# Thermocouple_datalogger_RevA.net
KiCad netlist of a schematic drawn in EAGLE
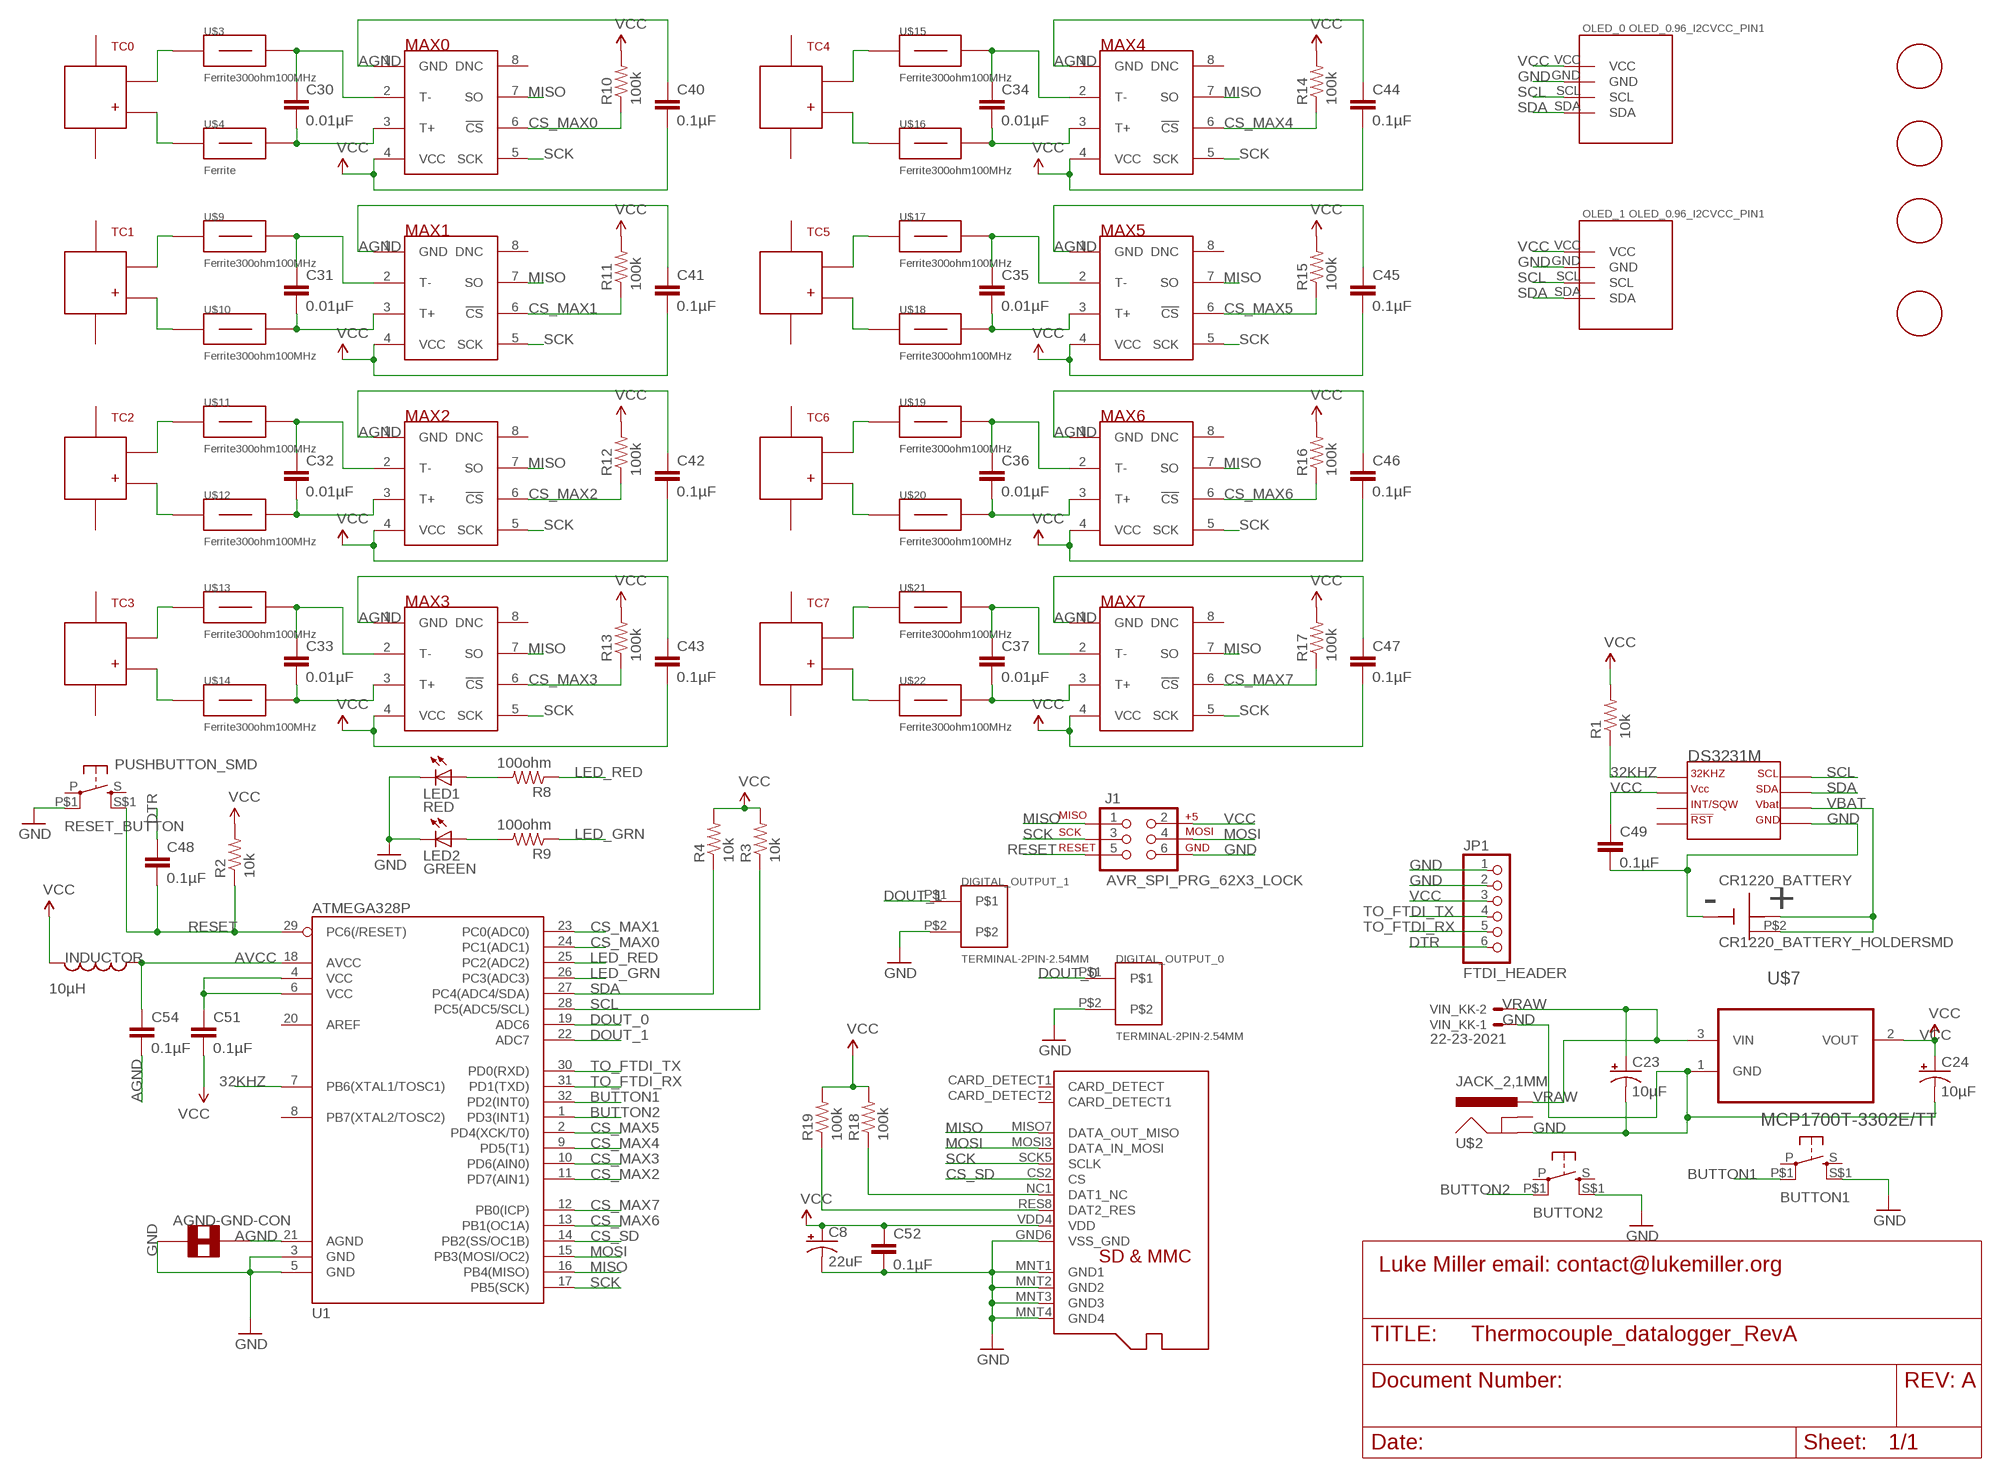
[diagram p0: schematic, sheet 1]

(export (version "E")
  (design (tool "Eeschema 10.0.6"))
  (components
    (comp (ref "AGND-GND-CON")
      (value "SOLDER_JUMPER_TRACESTANDARD")
      (footprint "eagle-import:SJ_2S-TRACE")
      (libsource (lib "eagle-import") (part "SOLDER_JUMPER_TRACESTANDARD"))
    )
    (comp (ref "BUTTON1")
      (value "PUSHBUTTON_DPST_SMDSTANDARD")
      (footprint "eagle-import:PUSHBUTTON_DPST_SMD")
      (libsource (lib "eagle-import") (part "PUSHBUTTON_DPST_SMDSTANDARD"))
    )
    (comp (ref "BUTTON2")
      (value "PUSHBUTTON_DPST_SMDSTANDARD")
      (footprint "eagle-import:PUSHBUTTON_DPST_SMD")
      (libsource (lib "eagle-import") (part "PUSHBUTTON_DPST_SMDSTANDARD"))
    )
    (comp (ref "C8")
      (value "22uF")
      (footprint "eagle-import:C0805_POL")
      (libsource (lib "eagle-import") (part "CPOL-US0805"))
    )
    (comp (ref "C23")
      (value "10µF")
      (footprint "eagle-import:PANASONIC_B")
      (libsource (lib "eagle-import") (part "CPOL-USB"))
    )
    (comp (ref "C24")
      (value "10µF")
      (footprint "eagle-import:PANASONIC_B")
      (libsource (lib "eagle-import") (part "CPOL-USB"))
    )
    (comp (ref "C30")
      (value "0.01µF")
      (footprint "eagle-import:0805")
      (libsource (lib "eagle-import") (part "CAP0805"))
    )
    (comp (ref "C31")
      (value "0.01µF")
      (footprint "eagle-import:0805")
      (libsource (lib "eagle-import") (part "CAP0805"))
    )
    (comp (ref "C32")
      (value "0.01µF")
      (footprint "eagle-import:0805")
      (libsource (lib "eagle-import") (part "CAP0805"))
    )
    (comp (ref "C33")
      (value "0.01µF")
      (footprint "eagle-import:0805")
      (libsource (lib "eagle-import") (part "CAP0805"))
    )
    (comp (ref "C34")
      (value "0.01µF")
      (footprint "eagle-import:0805")
      (libsource (lib "eagle-import") (part "CAP0805"))
    )
    (comp (ref "C35")
      (value "0.01µF")
      (footprint "eagle-import:0805")
      (libsource (lib "eagle-import") (part "CAP0805"))
    )
    (comp (ref "C36")
      (value "0.01µF")
      (footprint "eagle-import:0805")
      (libsource (lib "eagle-import") (part "CAP0805"))
    )
    (comp (ref "C37")
      (value "0.01µF")
      (footprint "eagle-import:0805")
      (libsource (lib "eagle-import") (part "CAP0805"))
    )
    (comp (ref "C40")
      (value "0.1µF")
      (footprint "eagle-import:0805")
      (libsource (lib "eagle-import") (part "CAP0805"))
    )
    (comp (ref "C41")
      (value "0.1µF")
      (footprint "eagle-import:0805")
      (libsource (lib "eagle-import") (part "CAP0805"))
    )
    (comp (ref "C42")
      (value "0.1µF")
      (footprint "eagle-import:0805")
      (libsource (lib "eagle-import") (part "CAP0805"))
    )
    (comp (ref "C43")
      (value "0.1µF")
      (footprint "eagle-import:0805")
      (libsource (lib "eagle-import") (part "CAP0805"))
    )
    (comp (ref "C44")
      (value "0.1µF")
      (footprint "eagle-import:0805")
      (libsource (lib "eagle-import") (part "CAP0805"))
    )
    (comp (ref "C45")
      (value "0.1µF")
      (footprint "eagle-import:0805")
      (libsource (lib "eagle-import") (part "CAP0805"))
    )
    (comp (ref "C46")
      (value "0.1µF")
      (footprint "eagle-import:0805")
      (libsource (lib "eagle-import") (part "CAP0805"))
    )
    (comp (ref "C47")
      (value "0.1µF")
      (footprint "eagle-import:0805")
      (libsource (lib "eagle-import") (part "CAP0805"))
    )
    (comp (ref "C48")
      (value "0.1µF")
      (footprint "eagle-import:0805")
      (libsource (lib "eagle-import") (part "CAP0805"))
    )
    (comp (ref "C49")
      (value "0.1µF")
      (footprint "eagle-import:0805")
      (libsource (lib "eagle-import") (part "CAP0805"))
    )
    (comp (ref "C51")
      (value "0.1µF")
      (footprint "eagle-import:0805")
      (libsource (lib "eagle-import") (part "CAP0805"))
    )
    (comp (ref "C52")
      (value "0.1µF")
      (footprint "eagle-import:0805")
      (libsource (lib "eagle-import") (part "CAP0805"))
    )
    (comp (ref "C54")
      (value "0.1µF")
      (footprint "eagle-import:0805")
      (libsource (lib "eagle-import") (part "CAP0805"))
    )
    (comp (ref "CR1220_BATTERY")
      (value "CR1220_BATTERY_HOLDERSMD")
      (footprint "eagle-import:CR1220_BATTERY_HOLDER_SMD")
      (libsource (lib "eagle-import") (part "CR1220_BATTERY_HOLDERSMD"))
    )
    (comp (ref "DIGITAL_OUTPUT_0")
      (value "TERMINAL-2PIN-2.54MM")
      (footprint "eagle-import:TERMINAL-2PIN-2.54MM")
      (libsource (lib "eagle-import") (part "TERMINAL-2PIN-2.54MM"))
    )
    (comp (ref "DIGITAL_OUTPUT_1")
      (value "TERMINAL-2PIN-2.54MM")
      (footprint "eagle-import:TERMINAL-2PIN-2.54MM")
      (libsource (lib "eagle-import") (part "TERMINAL-2PIN-2.54MM"))
    )
    (comp (ref "DS3231M")
      (value "DS3231MSOIC-8")
      (footprint "eagle-import:DS3231M_SOIC8")
      (libsource (lib "eagle-import") (part "DS3231MSOIC-8"))
    )
    (comp (ref "INDUCTOR")
      (value "10µH")
      (footprint "eagle-import:I_0805")
      (libsource (lib "eagle-import") (part "INDUCTOR0805_TY"))
    )
    (comp (ref "J1")
      (value "AVR_SPI_PRG_62X3_LOCK")
      (footprint "eagle-import:2X3_LOCK")
      (libsource (lib "eagle-import") (part "AVR_SPI_PRG_62X3_LOCK"))
    )
    (comp (ref "JP1")
      (value "FTDI_HEADER")
      (footprint "eagle-import:1X06-BIGLOCK")
      (libsource (lib "eagle-import") (part "PINHD-1X6LOCK"))
    )
    (comp (ref "LED1")
      (value "RED")
      (footprint "eagle-import:CHIPLED_0805")
      (libsource (lib "eagle-import") (part "LED0805"))
    )
    (comp (ref "LED2")
      (value "GREEN")
      (footprint "eagle-import:CHIPLED_0805")
      (libsource (lib "eagle-import") (part "LED0805"))
    )
    (comp (ref "MAX0")
      (value "MAX31855")
      (footprint "eagle-import:SO08")
      (libsource (lib "eagle-import") (part "MAX31855"))
    )
    (comp (ref "MAX1")
      (value "MAX31855")
      (footprint "eagle-import:SO08")
      (libsource (lib "eagle-import") (part "MAX31855"))
    )
    (comp (ref "MAX2")
      (value "MAX31855")
      (footprint "eagle-import:SO08")
      (libsource (lib "eagle-import") (part "MAX31855"))
    )
    (comp (ref "MAX3")
      (value "MAX31855")
      (footprint "eagle-import:SO08")
      (libsource (lib "eagle-import") (part "MAX31855"))
    )
    (comp (ref "MAX4")
      (value "MAX31855")
      (footprint "eagle-import:SO08")
      (libsource (lib "eagle-import") (part "MAX31855"))
    )
    (comp (ref "MAX5")
      (value "MAX31855")
      (footprint "eagle-import:SO08")
      (libsource (lib "eagle-import") (part "MAX31855"))
    )
    (comp (ref "MAX6")
      (value "MAX31855")
      (footprint "eagle-import:SO08")
      (libsource (lib "eagle-import") (part "MAX31855"))
    )
    (comp (ref "MAX7")
      (value "MAX31855")
      (footprint "eagle-import:SO08")
      (libsource (lib "eagle-import") (part "MAX31855"))
    )
    (comp (ref "OLED_0")
      (value "OLED_0.96_I2CVCC_PIN1")
      (footprint "eagle-import:OLED_0.96_I2C_VCC_PIN1")
      (libsource (lib "eagle-import") (part "OLED_0.96_I2CVCC_PIN1"))
    )
    (comp (ref "OLED_1")
      (value "OLED_0.96_I2CVCC_PIN1")
      (footprint "eagle-import:OLED_0.96_I2C_VCC_PIN1")
      (libsource (lib "eagle-import") (part "OLED_0.96_I2CVCC_PIN1"))
    )
    (comp (ref "R1")
      (value "10k")
      (footprint "eagle-import:R0805")
      (libsource (lib "eagle-import") (part "RESISTOR_SMDR0805"))
    )
    (comp (ref "R2")
      (value "10k")
      (footprint "eagle-import:R0805")
      (libsource (lib "eagle-import") (part "RESISTOR_SMDR0805"))
    )
    (comp (ref "R3")
      (value "10k")
      (footprint "eagle-import:R0805")
      (libsource (lib "eagle-import") (part "RESISTOR_SMDR0805"))
    )
    (comp (ref "R4")
      (value "10k")
      (footprint "eagle-import:R0805")
      (libsource (lib "eagle-import") (part "RESISTOR_SMDR0805"))
    )
    (comp (ref "R8")
      (value "100ohm")
      (footprint "eagle-import:R0805")
      (libsource (lib "eagle-import") (part "RESISTOR_SMDR0805"))
    )
    (comp (ref "R9")
      (value "100ohm")
      (footprint "eagle-import:R0805")
      (libsource (lib "eagle-import") (part "RESISTOR_SMDR0805"))
    )
    (comp (ref "R10")
      (value "100k")
      (footprint "eagle-import:R0805")
      (libsource (lib "eagle-import") (part "RESISTOR_SMDR0805"))
    )
    (comp (ref "R11")
      (value "100k")
      (footprint "eagle-import:R0805")
      (libsource (lib "eagle-import") (part "RESISTOR_SMDR0805"))
    )
    (comp (ref "R12")
      (value "100k")
      (footprint "eagle-import:R0805")
      (libsource (lib "eagle-import") (part "RESISTOR_SMDR0805"))
    )
    (comp (ref "R13")
      (value "100k")
      (footprint "eagle-import:R0805")
      (libsource (lib "eagle-import") (part "RESISTOR_SMDR0805"))
    )
    (comp (ref "R14")
      (value "100k")
      (footprint "eagle-import:R0805")
      (libsource (lib "eagle-import") (part "RESISTOR_SMDR0805"))
    )
    (comp (ref "R15")
      (value "100k")
      (footprint "eagle-import:R0805")
      (libsource (lib "eagle-import") (part "RESISTOR_SMDR0805"))
    )
    (comp (ref "R16")
      (value "100k")
      (footprint "eagle-import:R0805")
      (libsource (lib "eagle-import") (part "RESISTOR_SMDR0805"))
    )
    (comp (ref "R17")
      (value "100k")
      (footprint "eagle-import:R0805")
      (libsource (lib "eagle-import") (part "RESISTOR_SMDR0805"))
    )
    (comp (ref "R18")
      (value "100k")
      (footprint "eagle-import:R0805")
      (libsource (lib "eagle-import") (part "RESISTOR_SMDR0805"))
    )
    (comp (ref "R19")
      (value "100k")
      (footprint "eagle-import:R0805")
      (libsource (lib "eagle-import") (part "RESISTOR_SMDR0805"))
    )
    (comp (ref "RESET_BUTTON")
      (value "PUSHBUTTON_SMD")
      (footprint "eagle-import:PUSHBUTTON_DPST_SMD")
      (libsource (lib "eagle-import") (part "PUSHBUTTON_DPST_SMDSTANDARD"))
    )
    (comp (ref "TC0")
      (value "PCC-SMP-THERMOCOUPLEVERTICAL")
      (footprint "eagle-import:PCC-SMP-V")
      (libsource (lib "eagle-import") (part "PCC-SMP-THERMOCOUPLEVERTICAL"))
    )
    (comp (ref "TC1")
      (value "PCC-SMP-THERMOCOUPLEVERTICAL")
      (footprint "eagle-import:PCC-SMP-V")
      (libsource (lib "eagle-import") (part "PCC-SMP-THERMOCOUPLEVERTICAL"))
    )
    (comp (ref "TC2")
      (value "PCC-SMP-THERMOCOUPLEVERTICAL")
      (footprint "eagle-import:PCC-SMP-V")
      (libsource (lib "eagle-import") (part "PCC-SMP-THERMOCOUPLEVERTICAL"))
    )
    (comp (ref "TC3")
      (value "PCC-SMP-THERMOCOUPLEVERTICAL")
      (footprint "eagle-import:PCC-SMP-V")
      (libsource (lib "eagle-import") (part "PCC-SMP-THERMOCOUPLEVERTICAL"))
    )
    (comp (ref "TC4")
      (value "PCC-SMP-THERMOCOUPLEVERTICAL")
      (footprint "eagle-import:PCC-SMP-V")
      (libsource (lib "eagle-import") (part "PCC-SMP-THERMOCOUPLEVERTICAL"))
    )
    (comp (ref "TC5")
      (value "PCC-SMP-THERMOCOUPLEVERTICAL")
      (footprint "eagle-import:PCC-SMP-V")
      (libsource (lib "eagle-import") (part "PCC-SMP-THERMOCOUPLEVERTICAL"))
    )
    (comp (ref "TC6")
      (value "PCC-SMP-THERMOCOUPLEVERTICAL")
      (footprint "eagle-import:PCC-SMP-V")
      (libsource (lib "eagle-import") (part "PCC-SMP-THERMOCOUPLEVERTICAL"))
    )
    (comp (ref "TC7")
      (value "PCC-SMP-THERMOCOUPLEVERTICAL")
      (footprint "eagle-import:PCC-SMP-V")
      (libsource (lib "eagle-import") (part "PCC-SMP-THERMOCOUPLEVERTICAL"))
    )
    (comp (ref "U$2")
      (value "JACK_2,1MM")
      (footprint "eagle-import:POWER_JACK_DC_2,1MM")
      (libsource (lib "eagle-import") (part "POWER_JACK_2,1MM"))
    )
    (comp (ref "U$3")
      (value "Ferrite300ohm100MHz")
      (footprint "eagle-import:0805")
      (libsource (lib "eagle-import") (part "FERRITE_BEAD0805"))
    )
    (comp (ref "U$4")
      (value "Ferrite")
      (footprint "eagle-import:0805")
      (libsource (lib "eagle-import") (part "FERRITE_BEAD0805"))
    )
    (comp (ref "U$5")
      (value "MICROSD_MOLEX_REVERSECURRENT")
      (footprint "eagle-import:MICROSD_SOCKET_MOLEX_REVERSEMOUNT")
      (libsource (lib "eagle-import") (part "MICROSD_MOLEX_REVERSECURRENT"))
    )
    (comp (ref "U$6")
      (value "HOLE-LAYOUT4-40-SOCKET-HEAD")
      (footprint "eagle-import:4-40-SCREW-HOLE")
      (libsource (lib "eagle-import") (part "HOLE-LAYOUT4-40-SOCKET-HEAD"))
    )
    (comp (ref "U$7")
      (value "MCP1700T-3302E/TT")
      (footprint "eagle-import:SOT95P237X112-3N")
      (libsource (lib "eagle-import") (part "MCP1700T-3302E/TT"))
    )
    (comp (ref "U$9")
      (value "Ferrite300ohm100MHz")
      (footprint "eagle-import:0805")
      (libsource (lib "eagle-import") (part "FERRITE_BEAD0805"))
    )
    (comp (ref "U$10")
      (value "Ferrite300ohm100MHz")
      (footprint "eagle-import:0805")
      (libsource (lib "eagle-import") (part "FERRITE_BEAD0805"))
    )
    (comp (ref "U$11")
      (value "Ferrite300ohm100MHz")
      (footprint "eagle-import:0805")
      (libsource (lib "eagle-import") (part "FERRITE_BEAD0805"))
    )
    (comp (ref "U$12")
      (value "Ferrite300ohm100MHz")
      (footprint "eagle-import:0805")
      (libsource (lib "eagle-import") (part "FERRITE_BEAD0805"))
    )
    (comp (ref "U$13")
      (value "Ferrite300ohm100MHz")
      (footprint "eagle-import:0805")
      (libsource (lib "eagle-import") (part "FERRITE_BEAD0805"))
    )
    (comp (ref "U$14")
      (value "Ferrite300ohm100MHz")
      (footprint "eagle-import:0805")
      (libsource (lib "eagle-import") (part "FERRITE_BEAD0805"))
    )
    (comp (ref "U$15")
      (value "Ferrite300ohm100MHz")
      (footprint "eagle-import:0805")
      (libsource (lib "eagle-import") (part "FERRITE_BEAD0805"))
    )
    (comp (ref "U$16")
      (value "Ferrite300ohm100MHz")
      (footprint "eagle-import:0805")
      (libsource (lib "eagle-import") (part "FERRITE_BEAD0805"))
    )
    (comp (ref "U$17")
      (value "Ferrite300ohm100MHz")
      (footprint "eagle-import:0805")
      (libsource (lib "eagle-import") (part "FERRITE_BEAD0805"))
    )
    (comp (ref "U$18")
      (value "Ferrite300ohm100MHz")
      (footprint "eagle-import:0805")
      (libsource (lib "eagle-import") (part "FERRITE_BEAD0805"))
    )
    (comp (ref "U$19")
      (value "Ferrite300ohm100MHz")
      (footprint "eagle-import:0805")
      (libsource (lib "eagle-import") (part "FERRITE_BEAD0805"))
    )
    (comp (ref "U$20")
      (value "Ferrite300ohm100MHz")
      (footprint "eagle-import:0805")
      (libsource (lib "eagle-import") (part "FERRITE_BEAD0805"))
    )
    (comp (ref "U$21")
      (value "Ferrite300ohm100MHz")
      (footprint "eagle-import:0805")
      (libsource (lib "eagle-import") (part "FERRITE_BEAD0805"))
    )
    (comp (ref "U$22")
      (value "Ferrite300ohm100MHz")
      (footprint "eagle-import:0805")
      (libsource (lib "eagle-import") (part "FERRITE_BEAD0805"))
    )
    (comp (ref "U$23")
      (value "HOLE-LAYOUT4-40-SOCKET-HEAD")
      (footprint "eagle-import:4-40-SCREW-HOLE")
      (libsource (lib "eagle-import") (part "HOLE-LAYOUT4-40-SOCKET-HEAD"))
    )
    (comp (ref "U$24")
      (value "HOLE-LAYOUT4-40-SOCKET-HEAD")
      (footprint "eagle-import:4-40-SCREW-HOLE")
      (libsource (lib "eagle-import") (part "HOLE-LAYOUT4-40-SOCKET-HEAD"))
    )
    (comp (ref "U$25")
      (value "HOLE-LAYOUT4-40-SOCKET-HEAD")
      (footprint "eagle-import:4-40-SCREW-HOLE")
      (libsource (lib "eagle-import") (part "HOLE-LAYOUT4-40-SOCKET-HEAD"))
    )
    (comp (ref "U1")
      (value "ATMEGA328P")
      (footprint "eagle-import:TQFP32-08")
      (libsource (lib "eagle-import") (part "ATMEGA328_SMT"))
    )
    (comp (ref "VIN_KK")
      (value "22-23-2021")
      (footprint "eagle-import:22-23-2021")
      (fields (field (name "MF") "MOLEX"))
      (libsource (lib "eagle-import") (part "22-23-2021"))
    )
  )
  (nets
    (net (code "1") (name "/32KHZ") (class "Default")
      (node (ref "DS3231M") (pin "1") (pinfunction "P$1_32KHZ_1") (pintype "bidirectional"))
      (node (ref "R1") (pin "1") (pinfunction "1_1") (pintype "passive"))
      (node (ref "U1") (pin "7") (pinfunction "PB6(XTAL1/TOSC1)_7") (pintype "bidirectional"))
    )
    (net (code "2") (name "/AGND") (class "Default")
      (node (ref "AGND-GND-CON") (pin "2") (pinfunction "P$2_2") (pintype "bidirectional"))
      (node (ref "C40") (pin "1") (pinfunction "1_1") (pintype "passive"))
      (node (ref "C41") (pin "1") (pinfunction "1_1") (pintype "passive"))
      (node (ref "C42") (pin "1") (pinfunction "1_1") (pintype "passive"))
      (node (ref "C43") (pin "1") (pinfunction "1_1") (pintype "passive"))
      (node (ref "C44") (pin "1") (pinfunction "1_1") (pintype "passive"))
      (node (ref "C45") (pin "1") (pinfunction "1_1") (pintype "passive"))
      (node (ref "C46") (pin "1") (pinfunction "1_1") (pintype "passive"))
      (node (ref "C47") (pin "1") (pinfunction "1_1") (pintype "passive"))
      (node (ref "C54") (pin "2") (pinfunction "2_2") (pintype "passive"))
      (node (ref "MAX0") (pin "1") (pinfunction "GND_1") (pintype "power_in"))
      (node (ref "MAX1") (pin "1") (pinfunction "GND_1") (pintype "power_in"))
      (node (ref "MAX2") (pin "1") (pinfunction "GND_1") (pintype "power_in"))
      (node (ref "MAX3") (pin "1") (pinfunction "GND_1") (pintype "power_in"))
      (node (ref "MAX4") (pin "1") (pinfunction "GND_1") (pintype "power_in"))
      (node (ref "MAX5") (pin "1") (pinfunction "GND_1") (pintype "power_in"))
      (node (ref "MAX6") (pin "1") (pinfunction "GND_1") (pintype "power_in"))
      (node (ref "MAX7") (pin "1") (pinfunction "GND_1") (pintype "power_in"))
      (node (ref "U1") (pin "21") (pinfunction "AGND_21") (pintype "bidirectional"))
    )
    (net (code "3") (name "/AVCC") (class "Default")
      (node (ref "C54") (pin "1") (pinfunction "1_1") (pintype "passive"))
      (node (ref "INDUCTOR") (pin "P$1") (pinfunction "1_P$1") (pintype "passive"))
      (node (ref "U1") (pin "18") (pinfunction "AVCC_18") (pintype "bidirectional"))
    )
    (net (code "4") (name "/BUTTON1") (class "Default")
      (node (ref "BUTTON1") (pin "P$1") (pinfunction "P1_P$1") (pintype "passive"))
      (node (ref "U1") (pin "32") (pinfunction "PD2(INT0)_32") (pintype "bidirectional"))
    )
    (net (code "5") (name "/BUTTON2") (class "Default")
      (node (ref "BUTTON2") (pin "P$1") (pinfunction "P1_P$1") (pintype "passive"))
      (node (ref "U1") (pin "1") (pinfunction "PD3(INT1)_1") (pintype "bidirectional"))
    )
    (net (code "6") (name "/CS_MAX0") (class "Default")
      (node (ref "MAX0") (pin "6") (pinfunction "~{CS}_6") (pintype "bidirectional"))
      (node (ref "R10") (pin "1") (pinfunction "1_1") (pintype "passive"))
      (node (ref "U1") (pin "24") (pinfunction "PC1(ADC1)_24") (pintype "bidirectional"))
    )
    (net (code "7") (name "/CS_MAX1") (class "Default")
      (node (ref "MAX1") (pin "6") (pinfunction "~{CS}_6") (pintype "bidirectional"))
      (node (ref "R11") (pin "1") (pinfunction "1_1") (pintype "passive"))
      (node (ref "U1") (pin "23") (pinfunction "PC0(ADC0)_23") (pintype "bidirectional"))
    )
    (net (code "8") (name "/CS_MAX2") (class "Default")
      (node (ref "MAX2") (pin "6") (pinfunction "~{CS}_6") (pintype "bidirectional"))
      (node (ref "R12") (pin "1") (pinfunction "1_1") (pintype "passive"))
      (node (ref "U1") (pin "11") (pinfunction "PD7(AIN1)_11") (pintype "bidirectional"))
    )
    (net (code "9") (name "/CS_MAX3") (class "Default")
      (node (ref "MAX3") (pin "6") (pinfunction "~{CS}_6") (pintype "bidirectional"))
      (node (ref "R13") (pin "1") (pinfunction "1_1") (pintype "passive"))
      (node (ref "U1") (pin "10") (pinfunction "PD6(AIN0)_10") (pintype "bidirectional"))
    )
    (net (code "10") (name "/CS_MAX4") (class "Default")
      (node (ref "MAX4") (pin "6") (pinfunction "~{CS}_6") (pintype "bidirectional"))
      (node (ref "R14") (pin "1") (pinfunction "1_1") (pintype "passive"))
      (node (ref "U1") (pin "9") (pinfunction "PD5(T1)_9") (pintype "bidirectional"))
    )
    (net (code "11") (name "/CS_MAX5") (class "Default")
      (node (ref "MAX5") (pin "6") (pinfunction "~{CS}_6") (pintype "bidirectional"))
      (node (ref "R15") (pin "1") (pinfunction "1_1") (pintype "passive"))
      (node (ref "U1") (pin "2") (pinfunction "PD4(XCK/T0)_2") (pintype "bidirectional"))
    )
    (net (code "12") (name "/CS_MAX6") (class "Default")
      (node (ref "MAX6") (pin "6") (pinfunction "~{CS}_6") (pintype "bidirectional"))
      (node (ref "R16") (pin "1") (pinfunction "1_1") (pintype "passive"))
      (node (ref "U1") (pin "13") (pinfunction "PB1(OC1A)_13") (pintype "bidirectional"))
    )
    (net (code "13") (name "/CS_MAX7") (class "Default")
      (node (ref "MAX7") (pin "6") (pinfunction "~{CS}_6") (pintype "bidirectional"))
      (node (ref "R17") (pin "1") (pinfunction "1_1") (pintype "passive"))
      (node (ref "U1") (pin "12") (pinfunction "PB0(ICP)_12") (pintype "bidirectional"))
    )
    (net (code "14") (name "/CS_SD") (class "Default")
      (node (ref "U$5") (pin "CS2") (pinfunction "CS_CS2") (pintype "input"))
      (node (ref "U1") (pin "14") (pinfunction "PB2(SS/OC1B)_14") (pintype "bidirectional"))
    )
    (net (code "15") (name "/DOUT_0") (class "Default")
      (node (ref "DIGITAL_OUTPUT_0") (pin "P$1") (pinfunction "P$1_P$1") (pintype "bidirectional"))
      (node (ref "U1") (pin "19") (pinfunction "ADC6_19") (pintype "bidirectional"))
    )
    (net (code "16") (name "/DOUT_1") (class "Default")
      (node (ref "DIGITAL_OUTPUT_1") (pin "P$1") (pinfunction "P$1_P$1") (pintype "bidirectional"))
      (node (ref "U1") (pin "22") (pinfunction "ADC7_22") (pintype "bidirectional"))
    )
    (net (code "17") (name "/DTR") (class "Default")
      (node (ref "C48") (pin "1") (pinfunction "1_1") (pintype "passive"))
      (node (ref "JP1") (pin "6") (pinfunction "6_6") (pintype "passive"))
    )
    (net (code "18") (name "/LED_GRN") (class "Default")
      (node (ref "R9") (pin "1") (pinfunction "1_1") (pintype "passive"))
      (node (ref "U1") (pin "26") (pinfunction "PC3(ADC3)_26") (pintype "bidirectional"))
    )
    (net (code "19") (name "/LED_RED") (class "Default")
      (node (ref "R8") (pin "1") (pinfunction "1_1") (pintype "passive"))
      (node (ref "U1") (pin "25") (pinfunction "PC2(ADC2)_25") (pintype "bidirectional"))
    )
    (net (code "20") (name "/MISO") (class "Default")
      (node (ref "J1") (pin "1") (pinfunction "1_1") (pintype "passive"))
      (node (ref "MAX0") (pin "7") (pinfunction "SO_7") (pintype "bidirectional"))
      (node (ref "MAX1") (pin "7") (pinfunction "SO_7") (pintype "bidirectional"))
      (node (ref "MAX2") (pin "7") (pinfunction "SO_7") (pintype "bidirectional"))
      (node (ref "MAX3") (pin "7") (pinfunction "SO_7") (pintype "bidirectional"))
      (node (ref "MAX4") (pin "7") (pinfunction "SO_7") (pintype "bidirectional"))
      (node (ref "MAX5") (pin "7") (pinfunction "SO_7") (pintype "bidirectional"))
      (node (ref "MAX6") (pin "7") (pinfunction "SO_7") (pintype "bidirectional"))
      (node (ref "MAX7") (pin "7") (pinfunction "SO_7") (pintype "bidirectional"))
      (node (ref "U$5") (pin "MISO7") (pinfunction "DATA_OUT_MISO_MISO7") (pintype "output"))
      (node (ref "U1") (pin "16") (pinfunction "PB4(MISO)_16") (pintype "bidirectional"))
    )
    (net (code "21") (name "/MOSI") (class "Default")
      (node (ref "J1") (pin "4") (pinfunction "4_4") (pintype "passive"))
      (node (ref "U$5") (pin "MOSI3") (pinfunction "DATA_IN_MOSI_MOSI3") (pintype "input"))
      (node (ref "U1") (pin "15") (pinfunction "PB3(MOSI/OC2)_15") (pintype "bidirectional"))
    )
    (net (code "22") (name "/RESET") (class "Default")
      (node (ref "C48") (pin "2") (pinfunction "2_2") (pintype "passive"))
      (node (ref "J1") (pin "5") (pinfunction "5_5") (pintype "passive"))
      (node (ref "R2") (pin "1") (pinfunction "1_1") (pintype "passive"))
      (node (ref "RESET_BUTTON") (pin "S$1") (pinfunction "S1_S$1") (pintype "passive"))
      (node (ref "U1") (pin "29") (pinfunction "PC6(/RESET)_29") (pintype "bidirectional"))
    )
    (net (code "23") (name "/SCK") (class "Default")
      (node (ref "J1") (pin "3") (pinfunction "3_3") (pintype "passive"))
      (node (ref "MAX0") (pin "5") (pinfunction "SCK_5") (pintype "bidirectional"))
      (node (ref "MAX1") (pin "5") (pinfunction "SCK_5") (pintype "bidirectional"))
      (node (ref "MAX2") (pin "5") (pinfunction "SCK_5") (pintype "bidirectional"))
      (node (ref "MAX3") (pin "5") (pinfunction "SCK_5") (pintype "bidirectional"))
      (node (ref "MAX4") (pin "5") (pinfunction "SCK_5") (pintype "bidirectional"))
      (node (ref "MAX5") (pin "5") (pinfunction "SCK_5") (pintype "bidirectional"))
      (node (ref "MAX6") (pin "5") (pinfunction "SCK_5") (pintype "bidirectional"))
      (node (ref "MAX7") (pin "5") (pinfunction "SCK_5") (pintype "bidirectional"))
      (node (ref "U$5") (pin "SCK5") (pinfunction "SCLK_SCK5") (pintype "input"))
      (node (ref "U1") (pin "17") (pinfunction "PB5(SCK)_17") (pintype "bidirectional"))
    )
    (net (code "24") (name "/SCL") (class "Default")
      (node (ref "DS3231M") (pin "8") (pinfunction "P$8_SCL_8") (pintype "bidirectional"))
      (node (ref "OLED_0") (pin "SCL") (pinfunction "SCL_SCL") (pintype "bidirectional"))
      (node (ref "OLED_1") (pin "SCL") (pinfunction "SCL_SCL") (pintype "bidirectional"))
      (node (ref "R3") (pin "1") (pinfunction "1_1") (pintype "passive"))
      (node (ref "U1") (pin "28") (pinfunction "PC5(ADC5/SCL)_28") (pintype "bidirectional"))
    )
    (net (code "25") (name "/SDA") (class "Default")
      (node (ref "DS3231M") (pin "7") (pinfunction "P$7_SDA_7") (pintype "bidirectional"))
      (node (ref "OLED_0") (pin "SDA") (pinfunction "SDA_SDA") (pintype "bidirectional"))
      (node (ref "OLED_1") (pin "SDA") (pinfunction "SDA_SDA") (pintype "bidirectional"))
      (node (ref "R4") (pin "1") (pinfunction "1_1") (pintype "passive"))
      (node (ref "U1") (pin "27") (pinfunction "PC4(ADC4/SDA)_27") (pintype "bidirectional"))
    )
    (net (code "26") (name "/TO_FTDI_RX") (class "Default")
      (node (ref "JP1") (pin "5") (pinfunction "5_5") (pintype "passive"))
      (node (ref "U1") (pin "31") (pinfunction "PD1(TXD)_31") (pintype "bidirectional"))
    )
    (net (code "27") (name "/TO_FTDI_TX") (class "Default")
      (node (ref "JP1") (pin "4") (pinfunction "4_4") (pintype "passive"))
      (node (ref "U1") (pin "30") (pinfunction "PD0(RXD)_30") (pintype "bidirectional"))
    )
    (net (code "28") (name "/VBAT") (class "Default")
      (node (ref "CR1220_BATTERY") (pin "P$1") (pinfunction "VBAT_P$1") (pintype "power_in"))
      (node (ref "CR1220_BATTERY") (pin "P$2") (pinfunction "P$2_P$2") (pintype "power_in"))
      (node (ref "DS3231M") (pin "6") (pinfunction "P$6_VBAT_6") (pintype "bidirectional"))
    )
    (net (code "29") (name "/VRAW") (class "Default")
      (node (ref "C23") (pin "+") (pinfunction "+_+") (pintype "passive"))
      (node (ref "U$2") (pin "P$1") (pinfunction "PWR_P$1") (pintype "bidirectional"))
      (node (ref "U$7") (pin "3") (pinfunction "VIN_3") (pintype "input"))
      (node (ref "VIN_KK") (pin "2") (pinfunction "S_2") (pintype "passive"))
    )
    (net (code "30") (name "GND") (class "Default")
      (node (ref "AGND-GND-CON") (pin "1") (pinfunction "P$1_1") (pintype "bidirectional"))
      (node (ref "BUTTON1") (pin "S$1") (pinfunction "S1_S$1") (pintype "passive"))
      (node (ref "BUTTON2") (pin "S$1") (pinfunction "S1_S$1") (pintype "passive"))
      (node (ref "C23") (pin "-") (pinfunction "-_-") (pintype "passive"))
      (node (ref "C24") (pin "-") (pinfunction "-_-") (pintype "passive"))
      (node (ref "C49") (pin "2") (pinfunction "2_2") (pintype "passive"))
      (node (ref "C52") (pin "2") (pinfunction "2_2") (pintype "passive"))
      (node (ref "C8") (pin "P$2_C") (pinfunction "-_P$2_C") (pintype "passive"))
      (node (ref "CR1220_BATTERY") (pin "GND") (pinfunction "GND_GND") (pintype "power_in"))
      (node (ref "DIGITAL_OUTPUT_0") (pin "P$2") (pinfunction "P$2_P$2") (pintype "bidirectional"))
      (node (ref "DIGITAL_OUTPUT_1") (pin "P$2") (pinfunction "P$2_P$2") (pintype "bidirectional"))
      (node (ref "DS3231M") (pin "5") (pinfunction "P$5_GND_5") (pintype "power_in"))
      (node (ref "J1") (pin "6") (pinfunction "6_6") (pintype "passive"))
      (node (ref "JP1") (pin "1") (pinfunction "1_1") (pintype "passive"))
      (node (ref "JP1") (pin "2") (pinfunction "2_2") (pintype "passive"))
      (node (ref "LED1") (pin "C") (pinfunction "C_C") (pintype "passive"))
      (node (ref "LED2") (pin "C") (pinfunction "C_C") (pintype "passive"))
      (node (ref "OLED_0") (pin "GND") (pinfunction "GND_GND") (pintype "bidirectional"))
      (node (ref "OLED_1") (pin "GND") (pinfunction "GND_GND") (pintype "bidirectional"))
      (node (ref "RESET_BUTTON") (pin "P$1") (pinfunction "P1_P$1") (pintype "passive"))
      (node (ref "U$2") (pin "P$2") (pinfunction "GND_P$2") (pintype "bidirectional"))
      (node (ref "U$5") (pin "GND6") (pinfunction "VSS_GND_GND6") (pintype "power_in"))
      (node (ref "U$5") (pin "MNT1") (pinfunction "GND1_MNT1") (pintype "power_in"))
      (node (ref "U$5") (pin "MNT2") (pinfunction "GND2_MNT2") (pintype "power_in"))
      (node (ref "U$5") (pin "MNT3") (pinfunction "GND3_MNT3") (pintype "power_in"))
      (node (ref "U$5") (pin "MNT4") (pinfunction "GND4_MNT4") (pintype "power_in"))
      (node (ref "U$7") (pin "1") (pinfunction "GND_1") (pintype "passive"))
      (node (ref "U1") (pin "3") (pinfunction "GND_3") (pintype "bidirectional"))
      (node (ref "U1") (pin "5") (pinfunction "GND_5") (pintype "bidirectional"))
      (node (ref "VIN_KK") (pin "1") (pinfunction "S_1") (pintype "passive"))
    )
    (net (code "31") (name "Net-(C51-Pad1)") (class "Default")
      (node (ref "C51") (pin "1") (pinfunction "1_1") (pintype "passive"))
      (node (ref "U1") (pin "4") (pinfunction "VCC_4") (pintype "bidirectional"))
      (node (ref "U1") (pin "6") (pinfunction "VCC_6") (pintype "bidirectional"))
    )
    (net (code "32") (name "Net-(LED1-PadA)") (class "Default")
      (node (ref "LED1") (pin "A") (pinfunction "A_A") (pintype "passive"))
      (node (ref "R8") (pin "2") (pinfunction "2_2") (pintype "passive"))
    )
    (net (code "33") (name "Net-(LED2-PadA)") (class "Default")
      (node (ref "LED2") (pin "A") (pinfunction "A_A") (pintype "passive"))
      (node (ref "R9") (pin "2") (pinfunction "2_2") (pintype "passive"))
    )
    (net (code "34") (name "Net-(MAX0-T+)") (class "Default")
      (node (ref "C30") (pin "2") (pinfunction "2_2") (pintype "passive"))
      (node (ref "MAX0") (pin "3") (pinfunction "T+_3") (pintype "input"))
      (node (ref "U$4") (pin "2") (pinfunction "P$2_2") (pintype "bidirectional"))
    )
    (net (code "35") (name "Net-(MAX0-T-)") (class "Default")
      (node (ref "C30") (pin "1") (pinfunction "1_1") (pintype "passive"))
      (node (ref "MAX0") (pin "2") (pinfunction "T-_2") (pintype "input"))
      (node (ref "U$3") (pin "2") (pinfunction "P$2_2") (pintype "bidirectional"))
    )
    (net (code "36") (name "Net-(MAX1-T+)") (class "Default")
      (node (ref "C31") (pin "2") (pinfunction "2_2") (pintype "passive"))
      (node (ref "MAX1") (pin "3") (pinfunction "T+_3") (pintype "input"))
      (node (ref "U$10") (pin "2") (pinfunction "P$2_2") (pintype "bidirectional"))
    )
    (net (code "37") (name "Net-(MAX1-T-)") (class "Default")
      (node (ref "C31") (pin "1") (pinfunction "1_1") (pintype "passive"))
      (node (ref "MAX1") (pin "2") (pinfunction "T-_2") (pintype "input"))
      (node (ref "U$9") (pin "2") (pinfunction "P$2_2") (pintype "bidirectional"))
    )
    (net (code "38") (name "Net-(MAX2-T+)") (class "Default")
      (node (ref "C32") (pin "2") (pinfunction "2_2") (pintype "passive"))
      (node (ref "MAX2") (pin "3") (pinfunction "T+_3") (pintype "input"))
      (node (ref "U$12") (pin "2") (pinfunction "P$2_2") (pintype "bidirectional"))
    )
    (net (code "39") (name "Net-(MAX2-T-)") (class "Default")
      (node (ref "C32") (pin "1") (pinfunction "1_1") (pintype "passive"))
      (node (ref "MAX2") (pin "2") (pinfunction "T-_2") (pintype "input"))
      (node (ref "U$11") (pin "2") (pinfunction "P$2_2") (pintype "bidirectional"))
    )
    (net (code "40") (name "Net-(MAX3-T+)") (class "Default")
      (node (ref "C33") (pin "2") (pinfunction "2_2") (pintype "passive"))
      (node (ref "MAX3") (pin "3") (pinfunction "T+_3") (pintype "input"))
      (node (ref "U$14") (pin "2") (pinfunction "P$2_2") (pintype "bidirectional"))
    )
    (net (code "41") (name "Net-(MAX3-T-)") (class "Default")
      (node (ref "C33") (pin "1") (pinfunction "1_1") (pintype "passive"))
      (node (ref "MAX3") (pin "2") (pinfunction "T-_2") (pintype "input"))
      (node (ref "U$13") (pin "2") (pinfunction "P$2_2") (pintype "bidirectional"))
    )
    (net (code "42") (name "Net-(MAX4-T+)") (class "Default")
      (node (ref "C34") (pin "2") (pinfunction "2_2") (pintype "passive"))
      (node (ref "MAX4") (pin "3") (pinfunction "T+_3") (pintype "input"))
      (node (ref "U$16") (pin "2") (pinfunction "P$2_2") (pintype "bidirectional"))
    )
    (net (code "43") (name "Net-(MAX4-T-)") (class "Default")
      (node (ref "C34") (pin "1") (pinfunction "1_1") (pintype "passive"))
      (node (ref "MAX4") (pin "2") (pinfunction "T-_2") (pintype "input"))
      (node (ref "U$15") (pin "2") (pinfunction "P$2_2") (pintype "bidirectional"))
    )
    (net (code "44") (name "Net-(MAX5-T+)") (class "Default")
      (node (ref "C35") (pin "2") (pinfunction "2_2") (pintype "passive"))
      (node (ref "MAX5") (pin "3") (pinfunction "T+_3") (pintype "input"))
      (node (ref "U$18") (pin "2") (pinfunction "P$2_2") (pintype "bidirectional"))
    )
    (net (code "45") (name "Net-(MAX5-T-)") (class "Default")
      (node (ref "C35") (pin "1") (pinfunction "1_1") (pintype "passive"))
      (node (ref "MAX5") (pin "2") (pinfunction "T-_2") (pintype "input"))
      (node (ref "U$17") (pin "2") (pinfunction "P$2_2") (pintype "bidirectional"))
    )
    (net (code "46") (name "Net-(MAX6-T+)") (class "Default")
      (node (ref "C36") (pin "2") (pinfunction "2_2") (pintype "passive"))
      (node (ref "MAX6") (pin "3") (pinfunction "T+_3") (pintype "input"))
      (node (ref "U$20") (pin "2") (pinfunction "P$2_2") (pintype "bidirectional"))
    )
    (net (code "47") (name "Net-(MAX6-T-)") (class "Default")
      (node (ref "C36") (pin "1") (pinfunction "1_1") (pintype "passive"))
      (node (ref "MAX6") (pin "2") (pinfunction "T-_2") (pintype "input"))
      (node (ref "U$19") (pin "2") (pinfunction "P$2_2") (pintype "bidirectional"))
    )
    (net (code "48") (name "Net-(MAX7-T+)") (class "Default")
      (node (ref "C37") (pin "2") (pinfunction "2_2") (pintype "passive"))
      (node (ref "MAX7") (pin "3") (pinfunction "T+_3") (pintype "input"))
      (node (ref "U$22") (pin "2") (pinfunction "P$2_2") (pintype "bidirectional"))
    )
    (net (code "49") (name "Net-(MAX7-T-)") (class "Default")
      (node (ref "C37") (pin "1") (pinfunction "1_1") (pintype "passive"))
      (node (ref "MAX7") (pin "2") (pinfunction "T-_2") (pintype "input"))
      (node (ref "U$21") (pin "2") (pinfunction "P$2_2") (pintype "bidirectional"))
    )
    (net (code "50") (name "Net-(U$3-P$1)") (class "Default")
      (node (ref "TC0") (pin "P$1") (pinfunction "P$1_P$1") (pintype "bidirectional"))
      (node (ref "U$3") (pin "1") (pinfunction "P$1_1") (pintype "bidirectional"))
    )
    (net (code "51") (name "Net-(U$4-P$1)") (class "Default")
      (node (ref "TC0") (pin "P$2") (pinfunction "P$2_P$2") (pintype "bidirectional"))
      (node (ref "U$4") (pin "1") (pinfunction "P$1_1") (pintype "bidirectional"))
    )
    (net (code "52") (name "Net-(U$5-DAT1_NC)") (class "Default")
      (node (ref "R18") (pin "1") (pinfunction "1_1") (pintype "passive"))
      (node (ref "U$5") (pin "NC1") (pinfunction "DAT1_NC_NC1") (pintype "bidirectional"))
    )
    (net (code "53") (name "Net-(U$5-DAT2_RES)") (class "Default")
      (node (ref "R19") (pin "1") (pinfunction "1_1") (pintype "passive"))
      (node (ref "U$5") (pin "RES8") (pinfunction "DAT2_RES_RES8") (pintype "bidirectional"))
    )
    (net (code "54") (name "Net-(U$9-P$1)") (class "Default")
      (node (ref "TC1") (pin "P$1") (pinfunction "P$1_P$1") (pintype "bidirectional"))
      (node (ref "U$9") (pin "1") (pinfunction "P$1_1") (pintype "bidirectional"))
    )
    (net (code "55") (name "Net-(U$10-P$1)") (class "Default")
      (node (ref "TC1") (pin "P$2") (pinfunction "P$2_P$2") (pintype "bidirectional"))
      (node (ref "U$10") (pin "1") (pinfunction "P$1_1") (pintype "bidirectional"))
    )
    (net (code "56") (name "Net-(U$11-P$1)") (class "Default")
      (node (ref "TC2") (pin "P$1") (pinfunction "P$1_P$1") (pintype "bidirectional"))
      (node (ref "U$11") (pin "1") (pinfunction "P$1_1") (pintype "bidirectional"))
    )
    (net (code "57") (name "Net-(U$12-P$1)") (class "Default")
      (node (ref "TC2") (pin "P$2") (pinfunction "P$2_P$2") (pintype "bidirectional"))
      (node (ref "U$12") (pin "1") (pinfunction "P$1_1") (pintype "bidirectional"))
    )
    (net (code "58") (name "Net-(U$13-P$1)") (class "Default")
      (node (ref "TC3") (pin "P$1") (pinfunction "P$1_P$1") (pintype "bidirectional"))
      (node (ref "U$13") (pin "1") (pinfunction "P$1_1") (pintype "bidirectional"))
    )
    (net (code "59") (name "Net-(U$14-P$1)") (class "Default")
      (node (ref "TC3") (pin "P$2") (pinfunction "P$2_P$2") (pintype "bidirectional"))
      (node (ref "U$14") (pin "1") (pinfunction "P$1_1") (pintype "bidirectional"))
    )
    (net (code "60") (name "Net-(U$15-P$1)") (class "Default")
      (node (ref "TC4") (pin "P$1") (pinfunction "P$1_P$1") (pintype "bidirectional"))
      (node (ref "U$15") (pin "1") (pinfunction "P$1_1") (pintype "bidirectional"))
    )
    (net (code "61") (name "Net-(U$16-P$1)") (class "Default")
      (node (ref "TC4") (pin "P$2") (pinfunction "P$2_P$2") (pintype "bidirectional"))
      (node (ref "U$16") (pin "1") (pinfunction "P$1_1") (pintype "bidirectional"))
    )
    (net (code "62") (name "Net-(U$17-P$1)") (class "Default")
      (node (ref "TC5") (pin "P$1") (pinfunction "P$1_P$1") (pintype "bidirectional"))
      (node (ref "U$17") (pin "1") (pinfunction "P$1_1") (pintype "bidirectional"))
    )
    (net (code "63") (name "Net-(U$18-P$1)") (class "Default")
      (node (ref "TC5") (pin "P$2") (pinfunction "P$2_P$2") (pintype "bidirectional"))
      (node (ref "U$18") (pin "1") (pinfunction "P$1_1") (pintype "bidirectional"))
    )
    (net (code "64") (name "Net-(U$19-P$1)") (class "Default")
      (node (ref "TC6") (pin "P$1") (pinfunction "P$1_P$1") (pintype "bidirectional"))
      (node (ref "U$19") (pin "1") (pinfunction "P$1_1") (pintype "bidirectional"))
    )
    (net (code "65") (name "Net-(U$20-P$1)") (class "Default")
      (node (ref "TC6") (pin "P$2") (pinfunction "P$2_P$2") (pintype "bidirectional"))
      (node (ref "U$20") (pin "1") (pinfunction "P$1_1") (pintype "bidirectional"))
    )
    (net (code "66") (name "Net-(U$21-P$1)") (class "Default")
      (node (ref "TC7") (pin "P$1") (pinfunction "P$1_P$1") (pintype "bidirectional"))
      (node (ref "U$21") (pin "1") (pinfunction "P$1_1") (pintype "bidirectional"))
    )
    (net (code "67") (name "Net-(U$22-P$1)") (class "Default")
      (node (ref "TC7") (pin "P$2") (pinfunction "P$2_P$2") (pintype "bidirectional"))
      (node (ref "U$22") (pin "1") (pinfunction "P$1_1") (pintype "bidirectional"))
    )
    (net (code "68") (name "VCC") (class "Default")
      (node (ref "C24") (pin "+") (pinfunction "+_+") (pintype "passive"))
      (node (ref "C40") (pin "2") (pinfunction "2_2") (pintype "passive"))
      (node (ref "C41") (pin "2") (pinfunction "2_2") (pintype "passive"))
      (node (ref "C42") (pin "2") (pinfunction "2_2") (pintype "passive"))
      (node (ref "C43") (pin "2") (pinfunction "2_2") (pintype "passive"))
      (node (ref "C44") (pin "2") (pinfunction "2_2") (pintype "passive"))
      (node (ref "C45") (pin "2") (pinfunction "2_2") (pintype "passive"))
      (node (ref "C46") (pin "2") (pinfunction "2_2") (pintype "passive"))
      (node (ref "C47") (pin "2") (pinfunction "2_2") (pintype "passive"))
      (node (ref "C49") (pin "1") (pinfunction "1_1") (pintype "passive"))
      (node (ref "C51") (pin "2") (pinfunction "2_2") (pintype "passive"))
      (node (ref "C52") (pin "1") (pinfunction "1_1") (pintype "passive"))
      (node (ref "C8") (pin "P$1_A") (pinfunction "+_P$1_A") (pintype "passive"))
      (node (ref "DS3231M") (pin "2") (pinfunction "P$2_VCC_2") (pintype "power_in"))
      (node (ref "INDUCTOR") (pin "P$2") (pinfunction "2_P$2") (pintype "passive"))
      (node (ref "J1") (pin "2") (pinfunction "2_2") (pintype "passive"))
      (node (ref "JP1") (pin "3") (pinfunction "3_3") (pintype "passive"))
      (node (ref "MAX0") (pin "4") (pinfunction "VCC_4") (pintype "power_in"))
      (node (ref "MAX1") (pin "4") (pinfunction "VCC_4") (pintype "power_in"))
      (node (ref "MAX2") (pin "4") (pinfunction "VCC_4") (pintype "power_in"))
      (node (ref "MAX3") (pin "4") (pinfunction "VCC_4") (pintype "power_in"))
      (node (ref "MAX4") (pin "4") (pinfunction "VCC_4") (pintype "power_in"))
      (node (ref "MAX5") (pin "4") (pinfunction "VCC_4") (pintype "power_in"))
      (node (ref "MAX6") (pin "4") (pinfunction "VCC_4") (pintype "power_in"))
      (node (ref "MAX7") (pin "4") (pinfunction "VCC_4") (pintype "power_in"))
      (node (ref "OLED_0") (pin "VCC") (pinfunction "VCC_VCC") (pintype "bidirectional"))
      (node (ref "OLED_1") (pin "VCC") (pinfunction "VCC_VCC") (pintype "bidirectional"))
      (node (ref "R1") (pin "2") (pinfunction "2_2") (pintype "passive"))
      (node (ref "R10") (pin "2") (pinfunction "2_2") (pintype "passive"))
      (node (ref "R11") (pin "2") (pinfunction "2_2") (pintype "passive"))
      (node (ref "R12") (pin "2") (pinfunction "2_2") (pintype "passive"))
      (node (ref "R13") (pin "2") (pinfunction "2_2") (pintype "passive"))
      (node (ref "R14") (pin "2") (pinfunction "2_2") (pintype "passive"))
      (node (ref "R15") (pin "2") (pinfunction "2_2") (pintype "passive"))
      (node (ref "R16") (pin "2") (pinfunction "2_2") (pintype "passive"))
      (node (ref "R17") (pin "2") (pinfunction "2_2") (pintype "passive"))
      (node (ref "R18") (pin "2") (pinfunction "2_2") (pintype "passive"))
      (node (ref "R19") (pin "2") (pinfunction "2_2") (pintype "passive"))
      (node (ref "R2") (pin "2") (pinfunction "2_2") (pintype "passive"))
      (node (ref "R3") (pin "2") (pinfunction "2_2") (pintype "passive"))
      (node (ref "R4") (pin "2") (pinfunction "2_2") (pintype "passive"))
      (node (ref "U$5") (pin "VDD4") (pinfunction "VDD_VDD4") (pintype "power_in"))
      (node (ref "U$7") (pin "2") (pinfunction "VOUT_2") (pintype "output"))
    )
    (net (code "69") (name "unconnected-(BUTTON1-PadP)") (class "Default")
      (node (ref "BUTTON1") (pin "P") (pinfunction "P_P") (pintype "passive"))
    )
    (net (code "70") (name "unconnected-(BUTTON1-PadS)") (class "Default")
      (node (ref "BUTTON1") (pin "S") (pinfunction "S_S") (pintype "passive"))
    )
    (net (code "71") (name "unconnected-(BUTTON2-PadP)") (class "Default")
      (node (ref "BUTTON2") (pin "P") (pinfunction "P_P") (pintype "passive"))
    )
    (net (code "72") (name "unconnected-(BUTTON2-PadS)") (class "Default")
      (node (ref "BUTTON2") (pin "S") (pinfunction "S_S") (pintype "passive"))
    )
    (net (code "73") (name "unconnected-(DS3231M-P$3_INT-Pad3)") (class "Default")
      (node (ref "DS3231M") (pin "3") (pinfunction "P$3_INT_3") (pintype "bidirectional"))
    )
    (net (code "74") (name "unconnected-(DS3231M-P$4_RST-Pad4)") (class "Default")
      (node (ref "DS3231M") (pin "4") (pinfunction "P$4_RST_4") (pintype "bidirectional"))
    )
    (net (code "75") (name "unconnected-(MAX0-DNC-Pad8)") (class "Default")
      (node (ref "MAX0") (pin "8") (pinfunction "DNC_8") (pintype "no_connect"))
    )
    (net (code "76") (name "unconnected-(MAX1-DNC-Pad8)") (class "Default")
      (node (ref "MAX1") (pin "8") (pinfunction "DNC_8") (pintype "no_connect"))
    )
    (net (code "77") (name "unconnected-(MAX2-DNC-Pad8)") (class "Default")
      (node (ref "MAX2") (pin "8") (pinfunction "DNC_8") (pintype "no_connect"))
    )
    (net (code "78") (name "unconnected-(MAX3-DNC-Pad8)") (class "Default")
      (node (ref "MAX3") (pin "8") (pinfunction "DNC_8") (pintype "no_connect"))
    )
    (net (code "79") (name "unconnected-(MAX4-DNC-Pad8)") (class "Default")
      (node (ref "MAX4") (pin "8") (pinfunction "DNC_8") (pintype "no_connect"))
    )
    (net (code "80") (name "unconnected-(MAX5-DNC-Pad8)") (class "Default")
      (node (ref "MAX5") (pin "8") (pinfunction "DNC_8") (pintype "no_connect"))
    )
    (net (code "81") (name "unconnected-(MAX6-DNC-Pad8)") (class "Default")
      (node (ref "MAX6") (pin "8") (pinfunction "DNC_8") (pintype "no_connect"))
    )
    (net (code "82") (name "unconnected-(MAX7-DNC-Pad8)") (class "Default")
      (node (ref "MAX7") (pin "8") (pinfunction "DNC_8") (pintype "no_connect"))
    )
    (net (code "83") (name "unconnected-(RESET_BUTTON-PadP)") (class "Default")
      (node (ref "RESET_BUTTON") (pin "P") (pinfunction "P_P") (pintype "passive"))
    )
    (net (code "84") (name "unconnected-(RESET_BUTTON-PadS)") (class "Default")
      (node (ref "RESET_BUTTON") (pin "S") (pinfunction "S_S") (pintype "passive"))
    )
    (net (code "85") (name "unconnected-(TC0-PadP$3)") (class "Default")
      (node (ref "TC0") (pin "P$3") (pinfunction "P$3_P$3") (pintype "no_connect"))
    )
    (net (code "86") (name "unconnected-(TC0-PadP$4)") (class "Default")
      (node (ref "TC0") (pin "P$4") (pinfunction "P$4_P$4") (pintype "no_connect"))
    )
    (net (code "87") (name "unconnected-(TC1-PadP$3)") (class "Default")
      (node (ref "TC1") (pin "P$3") (pinfunction "P$3_P$3") (pintype "no_connect"))
    )
    (net (code "88") (name "unconnected-(TC1-PadP$4)") (class "Default")
      (node (ref "TC1") (pin "P$4") (pinfunction "P$4_P$4") (pintype "no_connect"))
    )
    (net (code "89") (name "unconnected-(TC2-PadP$3)") (class "Default")
      (node (ref "TC2") (pin "P$3") (pinfunction "P$3_P$3") (pintype "no_connect"))
    )
    (net (code "90") (name "unconnected-(TC2-PadP$4)") (class "Default")
      (node (ref "TC2") (pin "P$4") (pinfunction "P$4_P$4") (pintype "no_connect"))
    )
    (net (code "91") (name "unconnected-(TC3-PadP$3)") (class "Default")
      (node (ref "TC3") (pin "P$3") (pinfunction "P$3_P$3") (pintype "no_connect"))
    )
    (net (code "92") (name "unconnected-(TC3-PadP$4)") (class "Default")
      (node (ref "TC3") (pin "P$4") (pinfunction "P$4_P$4") (pintype "no_connect"))
    )
    (net (code "93") (name "unconnected-(TC4-PadP$3)") (class "Default")
      (node (ref "TC4") (pin "P$3") (pinfunction "P$3_P$3") (pintype "no_connect"))
    )
    (net (code "94") (name "unconnected-(TC4-PadP$4)") (class "Default")
      (node (ref "TC4") (pin "P$4") (pinfunction "P$4_P$4") (pintype "no_connect"))
    )
    (net (code "95") (name "unconnected-(TC5-PadP$3)") (class "Default")
      (node (ref "TC5") (pin "P$3") (pinfunction "P$3_P$3") (pintype "no_connect"))
    )
    (net (code "96") (name "unconnected-(TC5-PadP$4)") (class "Default")
      (node (ref "TC5") (pin "P$4") (pinfunction "P$4_P$4") (pintype "no_connect"))
    )
    (net (code "97") (name "unconnected-(TC6-PadP$3)") (class "Default")
      (node (ref "TC6") (pin "P$3") (pinfunction "P$3_P$3") (pintype "no_connect"))
    )
    (net (code "98") (name "unconnected-(TC6-PadP$4)") (class "Default")
      (node (ref "TC6") (pin "P$4") (pinfunction "P$4_P$4") (pintype "no_connect"))
    )
    (net (code "99") (name "unconnected-(TC7-PadP$3)") (class "Default")
      (node (ref "TC7") (pin "P$3") (pinfunction "P$3_P$3") (pintype "no_connect"))
    )
    (net (code "100") (name "unconnected-(TC7-PadP$4)") (class "Default")
      (node (ref "TC7") (pin "P$4") (pinfunction "P$4_P$4") (pintype "no_connect"))
    )
    (net (code "101") (name "unconnected-(U$2-GNDBREAK-PadP$3)") (class "Default")
      (node (ref "U$2") (pin "P$3") (pinfunction "GNDBREAK_P$3") (pintype "bidirectional"))
    )
    (net (code "102") (name "unconnected-(U$5-CARD_DETECT-PadCARD_DETECT1)") (class "Default")
      (node (ref "U$5") (pin "CARD_DETECT1") (pinfunction "CARD_DETECT_CARD_DETECT1") (pintype "passive"))
    )
    (net (code "103") (name "unconnected-(U$5-CARD_DETECT1-PadCARD_DETECT2)") (class "Default")
      (node (ref "U$5") (pin "CARD_DETECT2") (pinfunction "CARD_DETECT1_CARD_DETECT2") (pintype "passive"))
    )
    (net (code "104") (name "unconnected-(U1-AREF-Pad20)") (class "Default")
      (node (ref "U1") (pin "20") (pinfunction "AREF_20") (pintype "bidirectional"))
    )
    (net (code "105") (name "unconnected-(U1-PB7(XTAL2{slash}TOSC2)-Pad8)") (class "Default")
      (node (ref "U1") (pin "8") (pinfunction "PB7(XTAL2/TOSC2)_8") (pintype "bidirectional"))
    )
  )
)
